# msp430g2553in20-test-board.net
KiCad netlist of a schematic drawn in EAGLE
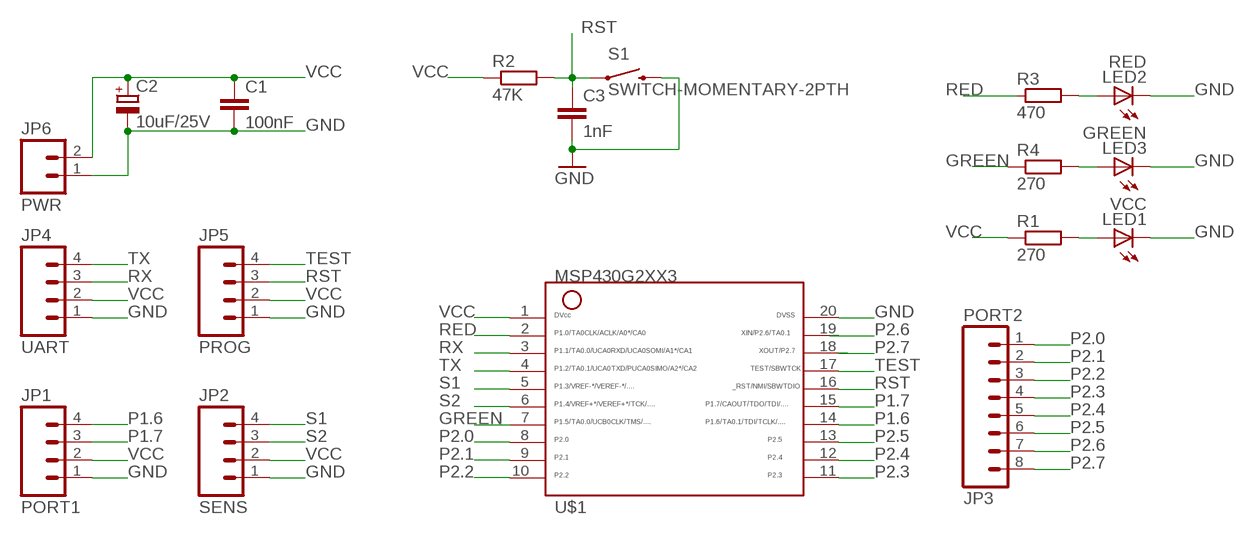
[diagram p0: schematic, sheet 1]

(export (version "E")
  (design (tool "Eeschema 10.0.6"))
  (components
    (comp (ref "C1")
      (value "100nF")
      (footprint "eagle-import:C025-025X050")
      (libsource (lib "eagle-import") (part "C-EU025-025X050"))
    )
    (comp (ref "C2")
      (value "10uF/25V")
      (footprint "eagle-import:E2-5")
      (libsource (lib "eagle-import") (part "CPOL-EUE2-5"))
    )
    (comp (ref "C3")
      (value "1nF")
      (footprint "eagle-import:C025-025X050")
      (libsource (lib "eagle-import") (part "C-EU025-025X050"))
    )
    (comp (ref "JP1")
      (value "PORT1")
      (footprint "eagle-import:1X04")
      (libsource (lib "eagle-import") (part "M04PTH"))
    )
    (comp (ref "JP2")
      (value "SENS")
      (footprint "eagle-import:1X04")
      (libsource (lib "eagle-import") (part "M04PTH"))
    )
    (comp (ref "JP3")
      (value "PORT2")
      (footprint "eagle-import:1X08")
      (libsource (lib "eagle-import") (part "M081X08"))
    )
    (comp (ref "JP4")
      (value "UART")
      (footprint "eagle-import:1X04")
      (libsource (lib "eagle-import") (part "M04PTH"))
    )
    (comp (ref "JP5")
      (value "PROG")
      (footprint "eagle-import:1X04")
      (libsource (lib "eagle-import") (part "M04PTH"))
    )
    (comp (ref "JP6")
      (value "PWR")
      (footprint "eagle-import:MOLEX-1X2")
      (libsource (lib "eagle-import") (part "M02POLAR"))
    )
    (comp (ref "LED1")
      (value "VCC")
      (footprint "eagle-import:LED3MM")
      (libsource (lib "eagle-import") (part "LED3MM"))
    )
    (comp (ref "LED2")
      (value "RED")
      (footprint "eagle-import:LED3MM")
      (libsource (lib "eagle-import") (part "LED3MM"))
    )
    (comp (ref "LED3")
      (value "GREEN")
      (footprint "eagle-import:LED3MM")
      (libsource (lib "eagle-import") (part "LED3MM"))
    )
    (comp (ref "R1")
      (value "270")
      (footprint "eagle-import:0204_5")
      (libsource (lib "eagle-import") (part "R-EU_0204/5"))
    )
    (comp (ref "R2")
      (value "47K")
      (footprint "eagle-import:0204_5")
      (libsource (lib "eagle-import") (part "R-EU_0204/5"))
    )
    (comp (ref "R3")
      (value "470")
      (footprint "eagle-import:0204_5")
      (libsource (lib "eagle-import") (part "R-EU_0204/5"))
    )
    (comp (ref "R4")
      (value "270")
      (footprint "eagle-import:0204_5")
      (libsource (lib "eagle-import") (part "R-EU_0204/5"))
    )
    (comp (ref "S1")
      (value "SWITCH-MOMENTARY-2PTH")
      (footprint "eagle-import:TACTILE-PTH")
      (libsource (lib "eagle-import") (part "SWITCH-MOMENTARY-2PTH"))
    )
    (comp (ref "U$1")
      (value "G2XX3---N20")
      (footprint "eagle-import:N20")
      (libsource (lib "eagle-import") (part "G2XX3---N20"))
    )
  )
  (nets
    (net (code "1") (name "/GREEN") (class "Default")
      (node (ref "R4") (pin "1") (pinfunction "1_1") (pintype "passive"))
      (node (ref "U$1") (pin "7") (pinfunction "7_7") (pintype "bidirectional"))
    )
    (net (code "2") (name "/P1.6") (class "Default")
      (node (ref "JP1") (pin "4") (pinfunction "4_4") (pintype "passive"))
      (node (ref "U$1") (pin "14") (pinfunction "14_14") (pintype "bidirectional"))
    )
    (net (code "3") (name "/P1.7") (class "Default")
      (node (ref "JP1") (pin "3") (pinfunction "3_3") (pintype "passive"))
      (node (ref "U$1") (pin "15") (pinfunction "15_15") (pintype "bidirectional"))
    )
    (net (code "4") (name "/P2.0") (class "Default")
      (node (ref "JP3") (pin "1") (pinfunction "1_1") (pintype "passive"))
      (node (ref "U$1") (pin "8") (pinfunction "8_8") (pintype "bidirectional"))
    )
    (net (code "5") (name "/P2.1") (class "Default")
      (node (ref "JP3") (pin "2") (pinfunction "2_2") (pintype "passive"))
      (node (ref "U$1") (pin "9") (pinfunction "9_9") (pintype "bidirectional"))
    )
    (net (code "6") (name "/P2.2") (class "Default")
      (node (ref "JP3") (pin "3") (pinfunction "3_3") (pintype "passive"))
      (node (ref "U$1") (pin "10") (pinfunction "10_10") (pintype "bidirectional"))
    )
    (net (code "7") (name "/P2.3") (class "Default")
      (node (ref "JP3") (pin "4") (pinfunction "4_4") (pintype "passive"))
      (node (ref "U$1") (pin "11") (pinfunction "11_11") (pintype "bidirectional"))
    )
    (net (code "8") (name "/P2.4") (class "Default")
      (node (ref "JP3") (pin "5") (pinfunction "5_5") (pintype "passive"))
      (node (ref "U$1") (pin "12") (pinfunction "12_12") (pintype "bidirectional"))
    )
    (net (code "9") (name "/P2.5") (class "Default")
      (node (ref "JP3") (pin "6") (pinfunction "6_6") (pintype "passive"))
      (node (ref "U$1") (pin "13") (pinfunction "13_13") (pintype "bidirectional"))
    )
    (net (code "10") (name "/P2.6") (class "Default")
      (node (ref "JP3") (pin "7") (pinfunction "7_7") (pintype "passive"))
      (node (ref "U$1") (pin "19") (pinfunction "19_19") (pintype "bidirectional"))
    )
    (net (code "11") (name "/P2.7") (class "Default")
      (node (ref "JP3") (pin "8") (pinfunction "8_8") (pintype "passive"))
      (node (ref "U$1") (pin "18") (pinfunction "18_18") (pintype "bidirectional"))
    )
    (net (code "12") (name "/RED") (class "Default")
      (node (ref "R3") (pin "1") (pinfunction "1_1") (pintype "passive"))
      (node (ref "U$1") (pin "2") (pinfunction "2_2") (pintype "bidirectional"))
    )
    (net (code "13") (name "/RST") (class "Default")
      (node (ref "C3") (pin "1") (pinfunction "1_1") (pintype "passive"))
      (node (ref "JP5") (pin "3") (pinfunction "3_3") (pintype "passive"))
      (node (ref "R2") (pin "2") (pinfunction "2_2") (pintype "passive"))
      (node (ref "S1") (pin "1") (pinfunction "1_1") (pintype "passive"))
      (node (ref "U$1") (pin "16") (pinfunction "16_16") (pintype "bidirectional"))
    )
    (net (code "14") (name "/RX") (class "Default")
      (node (ref "JP4") (pin "3") (pinfunction "3_3") (pintype "passive"))
      (node (ref "U$1") (pin "3") (pinfunction "3_3") (pintype "bidirectional"))
    )
    (net (code "15") (name "/S1") (class "Default")
      (node (ref "JP2") (pin "4") (pinfunction "4_4") (pintype "passive"))
      (node (ref "U$1") (pin "5") (pinfunction "5_5") (pintype "bidirectional"))
    )
    (net (code "16") (name "/S2") (class "Default")
      (node (ref "JP2") (pin "3") (pinfunction "3_3") (pintype "passive"))
      (node (ref "U$1") (pin "6") (pinfunction "6_6") (pintype "bidirectional"))
    )
    (net (code "17") (name "/TEST") (class "Default")
      (node (ref "JP5") (pin "4") (pinfunction "4_4") (pintype "passive"))
      (node (ref "U$1") (pin "17") (pinfunction "17_17") (pintype "bidirectional"))
    )
    (net (code "18") (name "/TX") (class "Default")
      (node (ref "JP4") (pin "4") (pinfunction "4_4") (pintype "passive"))
      (node (ref "U$1") (pin "4") (pinfunction "4_4") (pintype "bidirectional"))
    )
    (net (code "19") (name "/VCC") (class "Default")
      (node (ref "C1") (pin "1") (pinfunction "1_1") (pintype "passive"))
      (node (ref "C2") (pin "+") (pinfunction "+_+") (pintype "passive"))
      (node (ref "JP1") (pin "2") (pinfunction "2_2") (pintype "passive"))
      (node (ref "JP2") (pin "2") (pinfunction "2_2") (pintype "passive"))
      (node (ref "JP4") (pin "2") (pinfunction "2_2") (pintype "passive"))
      (node (ref "JP5") (pin "2") (pinfunction "2_2") (pintype "passive"))
      (node (ref "JP6") (pin "2") (pinfunction "2_2") (pintype "passive"))
      (node (ref "R1") (pin "1") (pinfunction "1_1") (pintype "passive"))
      (node (ref "R2") (pin "1") (pinfunction "1_1") (pintype "passive"))
      (node (ref "U$1") (pin "1") (pinfunction "1_1") (pintype "bidirectional"))
    )
    (net (code "20") (name "GND") (class "Default")
      (node (ref "C1") (pin "2") (pinfunction "2_2") (pintype "passive"))
      (node (ref "C2") (pin "-") (pinfunction "-_-") (pintype "passive"))
      (node (ref "C3") (pin "2") (pinfunction "2_2") (pintype "passive"))
      (node (ref "JP1") (pin "1") (pinfunction "1_1") (pintype "passive"))
      (node (ref "JP2") (pin "1") (pinfunction "1_1") (pintype "passive"))
      (node (ref "JP4") (pin "1") (pinfunction "1_1") (pintype "passive"))
      (node (ref "JP5") (pin "1") (pinfunction "1_1") (pintype "passive"))
      (node (ref "JP6") (pin "1") (pinfunction "1_1") (pintype "passive"))
      (node (ref "LED1") (pin "K") (pinfunction "C_K") (pintype "passive"))
      (node (ref "LED2") (pin "K") (pinfunction "C_K") (pintype "passive"))
      (node (ref "LED3") (pin "K") (pinfunction "C_K") (pintype "passive"))
      (node (ref "S1") (pin "3") (pinfunction "2_3") (pintype "passive"))
      (node (ref "U$1") (pin "20") (pinfunction "20_20") (pintype "bidirectional"))
    )
    (net (code "21") (name "Net-(LED1-PadA)") (class "Default")
      (node (ref "LED1") (pin "A") (pinfunction "A_A") (pintype "passive"))
      (node (ref "R1") (pin "2") (pinfunction "2_2") (pintype "passive"))
    )
    (net (code "22") (name "Net-(LED2-PadA)") (class "Default")
      (node (ref "LED2") (pin "A") (pinfunction "A_A") (pintype "passive"))
      (node (ref "R3") (pin "2") (pinfunction "2_2") (pintype "passive"))
    )
    (net (code "23") (name "Net-(LED3-PadA)") (class "Default")
      (node (ref "LED3") (pin "A") (pinfunction "A_A") (pintype "passive"))
      (node (ref "R4") (pin "2") (pinfunction "2_2") (pintype "passive"))
    )
  )
)
